# 555_piano.net
KiCad netlist of a schematic drawn in EAGLE
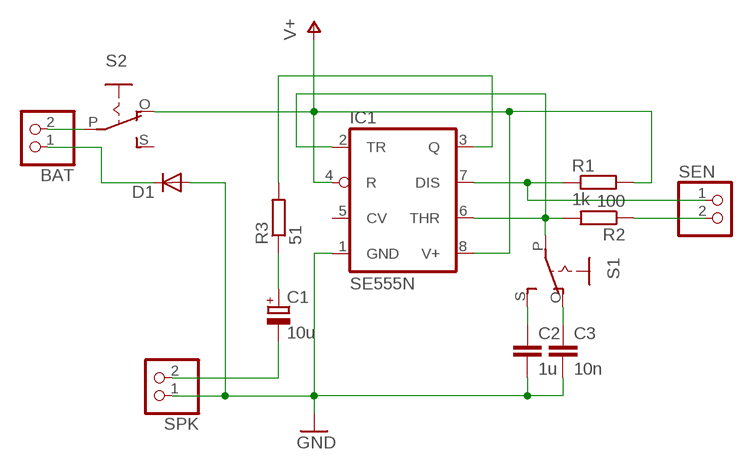
[diagram p0: schematic, sheet 1]

(export (version "E")
  (design (tool "Eeschema 10.0.6"))
  (components
    (comp (ref "BAT")
      (value "PINHD-1X2")
      (footprint "eagle-import:1X02")
      (libsource (lib "eagle-import") (part "PINHD-1X2"))
    )
    (comp (ref "C1")
      (value "10u")
      (footprint "eagle-import:TT2D5L")
      (libsource (lib "eagle-import") (part "CPOL-EUTT2D5L"))
    )
    (comp (ref "C2")
      (value "1u")
      (footprint "eagle-import:C025-025X050")
      (libsource (lib "eagle-import") (part "C-EU025-025X050"))
    )
    (comp (ref "C3")
      (value "10n")
      (footprint "eagle-import:C025-025X050")
      (libsource (lib "eagle-import") (part "C-EU025-025X050"))
    )
    (comp (ref "D1")
      (value "DIODE-D-5")
      (footprint "eagle-import:D-5")
      (libsource (lib "eagle-import") (part "DIODE-D-5"))
    )
    (comp (ref "IC1")
      (value "SE555N")
      (footprint "eagle-import:DIL08-ROUND")
      (libsource (lib "eagle-import") (part "555NSE"))
    )
    (comp (ref "R1")
      (value "1k")
      (footprint "eagle-import:0204_7")
      (libsource (lib "eagle-import") (part "R-EU_0204/7"))
    )
    (comp (ref "R2")
      (value "100")
      (footprint "eagle-import:0204_7")
      (libsource (lib "eagle-import") (part "R-EU_0204/7"))
    )
    (comp (ref "R3")
      (value "51")
      (footprint "eagle-import:0204_7")
      (libsource (lib "eagle-import") (part "R-EU_0204/7"))
    )
    (comp (ref "S1")
      (value "EG1218S")
      (footprint "eagle-import:EG1218")
      (libsource (lib "eagle-import") (part "EG1218S"))
    )
    (comp (ref "S2")
      (value "EG1218S")
      (footprint "eagle-import:EG1218")
      (libsource (lib "eagle-import") (part "EG1218S"))
    )
    (comp (ref "SEN")
      (value "PINHD-1X2")
      (footprint "eagle-import:1X02")
      (libsource (lib "eagle-import") (part "PINHD-1X2"))
    )
    (comp (ref "SPK")
      (value "PINHD-1X2")
      (footprint "eagle-import:1X02")
      (libsource (lib "eagle-import") (part "PINHD-1X2"))
    )
  )
  (nets
    (net (code "1") (name "GND") (class "Default")
      (node (ref "C2") (pin "2") (pinfunction "2_2") (pintype "passive"))
      (node (ref "C3") (pin "2") (pinfunction "2_2") (pintype "passive"))
      (node (ref "D1") (pin "A") (pinfunction "A_A") (pintype "passive"))
      (node (ref "IC1") (pin "1") (pinfunction "GND_1") (pintype "power_in"))
      (node (ref "SPK") (pin "1") (pinfunction "1_1") (pintype "passive"))
    )
    (net (code "2") (name "Net-(BAT-Pad1)") (class "Default")
      (node (ref "BAT") (pin "1") (pinfunction "1_1") (pintype "passive"))
      (node (ref "D1") (pin "C") (pinfunction "C_C") (pintype "passive"))
    )
    (net (code "3") (name "Net-(BAT-Pad2)") (class "Default")
      (node (ref "BAT") (pin "2") (pinfunction "2_2") (pintype "passive"))
      (node (ref "S2") (pin "P") (pinfunction "P_P") (pintype "passive"))
    )
    (net (code "4") (name "Net-(C1-Pad+)") (class "Default")
      (node (ref "C1") (pin "+") (pinfunction "+_+") (pintype "passive"))
      (node (ref "R3") (pin "1") (pinfunction "1_1") (pintype "passive"))
    )
    (net (code "5") (name "Net-(C1-Pad-)") (class "Default")
      (node (ref "C1") (pin "-") (pinfunction "-_-") (pintype "passive"))
      (node (ref "SPK") (pin "2") (pinfunction "2_2") (pintype "passive"))
    )
    (net (code "6") (name "Net-(C2-Pad1)") (class "Default")
      (node (ref "C2") (pin "1") (pinfunction "1_1") (pintype "passive"))
      (node (ref "S1") (pin "S") (pinfunction "S_S") (pintype "passive"))
    )
    (net (code "7") (name "Net-(C3-Pad1)") (class "Default")
      (node (ref "C3") (pin "1") (pinfunction "1_1") (pintype "passive"))
      (node (ref "S1") (pin "O") (pinfunction "O_O") (pintype "passive"))
    )
    (net (code "8") (name "Net-(IC1-DIS)") (class "Default")
      (node (ref "IC1") (pin "7") (pinfunction "DIS_7") (pintype "input"))
      (node (ref "R1") (pin "1") (pinfunction "1_1") (pintype "passive"))
      (node (ref "SEN") (pin "1") (pinfunction "1_1") (pintype "passive"))
    )
    (net (code "9") (name "Net-(IC1-Q)") (class "Default")
      (node (ref "IC1") (pin "3") (pinfunction "Q_3") (pintype "output"))
      (node (ref "R3") (pin "2") (pinfunction "2_2") (pintype "passive"))
    )
    (net (code "10") (name "Net-(IC1-THR)") (class "Default")
      (node (ref "IC1") (pin "2") (pinfunction "TR_2") (pintype "input"))
      (node (ref "IC1") (pin "6") (pinfunction "THR_6") (pintype "input"))
      (node (ref "R2") (pin "2") (pinfunction "2_2") (pintype "passive"))
      (node (ref "S1") (pin "P") (pinfunction "P_P") (pintype "passive"))
    )
    (net (code "11") (name "Net-(R2-Pad1)") (class "Default")
      (node (ref "R2") (pin "1") (pinfunction "1_1") (pintype "passive"))
      (node (ref "SEN") (pin "2") (pinfunction "2_2") (pintype "passive"))
    )
    (net (code "12") (name "V+") (class "Default")
      (node (ref "IC1") (pin "4") (pinfunction "R_4") (pintype "input"))
      (node (ref "IC1") (pin "8") (pinfunction "V+_8") (pintype "power_in"))
      (node (ref "R1") (pin "2") (pinfunction "2_2") (pintype "passive"))
      (node (ref "S2") (pin "O") (pinfunction "O_O") (pintype "passive"))
    )
    (net (code "13") (name "unconnected-(IC1-CV-Pad5)") (class "Default")
      (node (ref "IC1") (pin "5") (pinfunction "CV_5") (pintype "input"))
    )
    (net (code "14") (name "unconnected-(S2-PadS)") (class "Default")
      (node (ref "S2") (pin "S") (pinfunction "S_S") (pintype "passive"))
    )
  )
)
